# 1__schdoc.net
KiCad netlist of a schematic drawn in Altium Designer
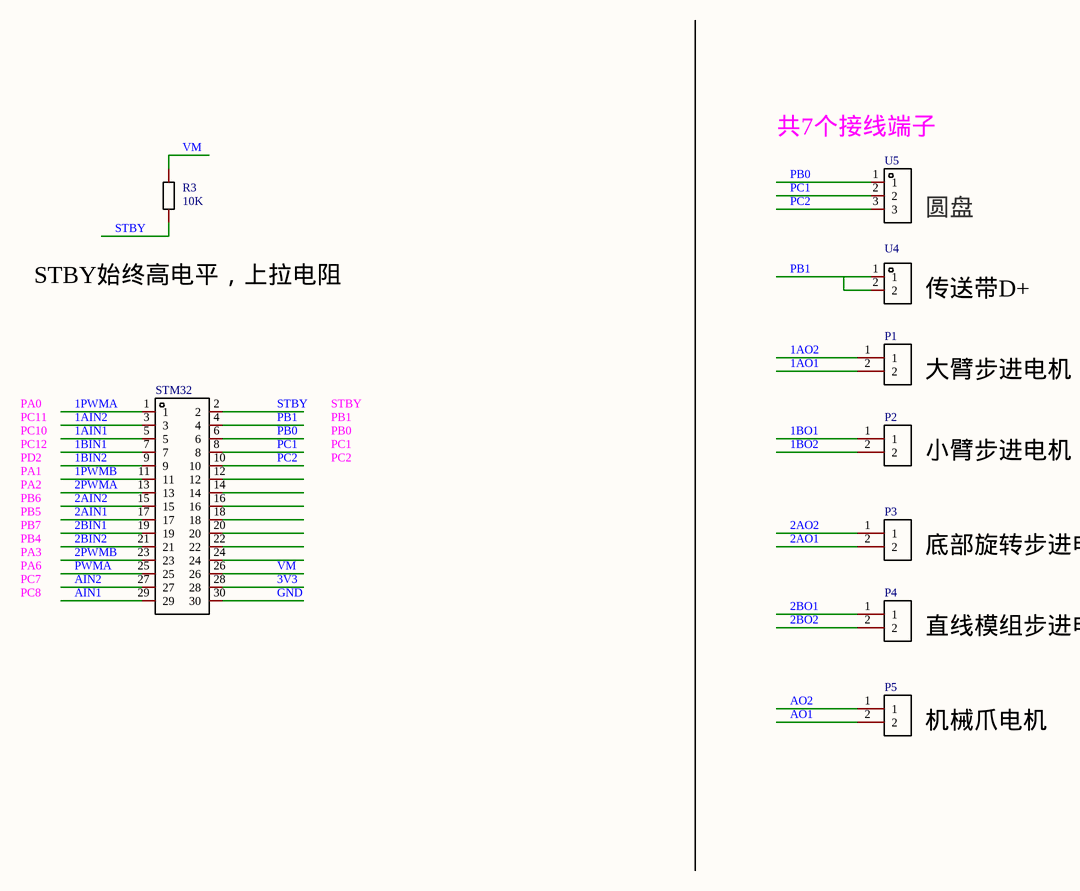
[diagram p0: 1_接口.schdoc.schdoc]

(export (version "E")
  (design (tool "Eeschema 10.0.6"))
  (components
    (comp (ref "P1")
      (value "WJ500V-5.08-2P")
      (fields (field (name "MANUFACTURER") "KANGNEX(康奈克斯电气)"))
      (libsource (lib "altium-import") (part "root_3_WJ500V-5.08-2P_"))
    )
    (comp (ref "P2")
      (value "WJ500V-5.08-2P")
      (fields (field (name "MANUFACTURER") "KANGNEX(康奈克斯电气)"))
      (libsource (lib "altium-import") (part "root_3_WJ500V-5.08-2P_"))
    )
    (comp (ref "P3")
      (value "WJ500V-5.08-2P")
      (fields (field (name "MANUFACTURER") "KANGNEX(康奈克斯电气)"))
      (libsource (lib "altium-import") (part "root_3_WJ500V-5.08-2P_"))
    )
    (comp (ref "P4")
      (value "WJ500V-5.08-2P")
      (fields (field (name "MANUFACTURER") "KANGNEX(康奈克斯电气)"))
      (libsource (lib "altium-import") (part "root_3_WJ500V-5.08-2P_"))
    )
    (comp (ref "P5")
      (value "WJ500V-5.08-2P")
      (fields (field (name "MANUFACTURER") "KANGNEX(康奈克斯电气)"))
      (libsource (lib "altium-import") (part "root_3_WJ500V-5.08-2P_"))
    )
    (comp (ref "R3")
      (value "10K")
      (fields (field (name "NAME") "10K"))
      (libsource (lib "altium-import") (part "root_1_Res_0603_"))
    )
    (comp (ref "STM32")
      (value "PM254-2-15-Z-8.5")
      (fields (field (name "MANUFACTURER") "HCTL(华灿天禄)"))
      (libsource (lib "altium-import") (part "root_0_PM254-2-15-Z-8.5_"))
    )
    (comp (ref "U4")
      (value "DB136HA-10.16-1P-S")
      (description "结构:1x1P;间距:10.16mm;颜色:绿色;安装方式:直插;额定电流:65A;额定电压:600V;排数:1;线规 - AWG:6~20;每排PIN数:1;工作温度范围:-40℃~+105℃;")
      (fields (field (name "MANUFACTURER") "DORABO(地博电气)"))
      (libsource (lib "altium-import") (part "root_0_DB136HA-10.16-1P-S_"))
    )
    (comp (ref "U5")
      (value "XY128V-A-5.08-3P")
      (fields (field (name "MANUFACTURER") "XINLAIYA(新莱亚)"))
      (libsource (lib "altium-import") (part "root_0_XY128V-A-5.08-3P_"))
    )
  )
  (nets
    (net (code "1") (name "/1AIN1") (class "Default")
      (node (ref "STM32") (pin "5") (pinfunction "5_5") (pintype "passive"))
    )
    (net (code "2") (name "/1AIN2") (class "Default")
      (node (ref "STM32") (pin "3") (pinfunction "3_3") (pintype "passive"))
    )
    (net (code "3") (name "/1AO1") (class "Default")
      (node (ref "P1") (pin "2") (pinfunction "2_2") (pintype "passive"))
    )
    (net (code "4") (name "/1AO2") (class "Default")
      (node (ref "P1") (pin "1") (pinfunction "1_1") (pintype "passive"))
    )
    (net (code "5") (name "/1BIN1") (class "Default")
      (node (ref "STM32") (pin "7") (pinfunction "7_7") (pintype "passive"))
    )
    (net (code "6") (name "/1BIN2") (class "Default")
      (node (ref "STM32") (pin "9") (pinfunction "9_9") (pintype "passive"))
    )
    (net (code "7") (name "/1BO1") (class "Default")
      (node (ref "P2") (pin "1") (pinfunction "1_1") (pintype "passive"))
    )
    (net (code "8") (name "/1BO2") (class "Default")
      (node (ref "P2") (pin "2") (pinfunction "2_2") (pintype "passive"))
    )
    (net (code "9") (name "/1PWMA") (class "Default")
      (node (ref "STM32") (pin "1") (pinfunction "1_1") (pintype "passive"))
    )
    (net (code "10") (name "/1PWMB") (class "Default")
      (node (ref "STM32") (pin "11") (pinfunction "11_11") (pintype "passive"))
    )
    (net (code "11") (name "/2AIN1") (class "Default")
      (node (ref "STM32") (pin "17") (pinfunction "17_17") (pintype "passive"))
    )
    (net (code "12") (name "/2AIN2") (class "Default")
      (node (ref "STM32") (pin "15") (pinfunction "15_15") (pintype "passive"))
    )
    (net (code "13") (name "/2AO1") (class "Default")
      (node (ref "P3") (pin "2") (pinfunction "2_2") (pintype "passive"))
    )
    (net (code "14") (name "/2AO2") (class "Default")
      (node (ref "P3") (pin "1") (pinfunction "1_1") (pintype "passive"))
    )
    (net (code "15") (name "/2BIN1") (class "Default")
      (node (ref "STM32") (pin "19") (pinfunction "19_19") (pintype "passive"))
    )
    (net (code "16") (name "/2BIN2") (class "Default")
      (node (ref "STM32") (pin "21") (pinfunction "21_21") (pintype "passive"))
    )
    (net (code "17") (name "/2BO1") (class "Default")
      (node (ref "P4") (pin "1") (pinfunction "1_1") (pintype "passive"))
    )
    (net (code "18") (name "/2BO2") (class "Default")
      (node (ref "P4") (pin "2") (pinfunction "2_2") (pintype "passive"))
    )
    (net (code "19") (name "/2PWMA") (class "Default")
      (node (ref "STM32") (pin "13") (pinfunction "13_13") (pintype "passive"))
    )
    (net (code "20") (name "/2PWMB") (class "Default")
      (node (ref "STM32") (pin "23") (pinfunction "23_23") (pintype "passive"))
    )
    (net (code "21") (name "/3V3") (class "Default")
      (node (ref "STM32") (pin "28") (pinfunction "28_28") (pintype "passive"))
    )
    (net (code "22") (name "/AIN1") (class "Default")
      (node (ref "STM32") (pin "29") (pinfunction "29_29") (pintype "passive"))
    )
    (net (code "23") (name "/AIN2") (class "Default")
      (node (ref "STM32") (pin "27") (pinfunction "27_27") (pintype "passive"))
    )
    (net (code "24") (name "/AO1") (class "Default")
      (node (ref "P5") (pin "2") (pinfunction "2_2") (pintype "passive"))
    )
    (net (code "25") (name "/AO2") (class "Default")
      (node (ref "P5") (pin "1") (pinfunction "1_1") (pintype "passive"))
    )
    (net (code "26") (name "/GND") (class "Default")
      (node (ref "STM32") (pin "30") (pinfunction "30_30") (pintype "passive"))
    )
    (net (code "27") (name "/PB0") (class "Default")
      (node (ref "STM32") (pin "6") (pinfunction "6_6") (pintype "passive"))
      (node (ref "U5") (pin "1") (pinfunction "1_1") (pintype "passive"))
    )
    (net (code "28") (name "/PB1") (class "Default")
      (node (ref "STM32") (pin "4") (pinfunction "4_4") (pintype "passive"))
      (node (ref "U4") (pin "1") (pinfunction "1_1") (pintype "passive"))
      (node (ref "U4") (pin "2") (pinfunction "2_2") (pintype "passive"))
    )
    (net (code "29") (name "/PC1") (class "Default")
      (node (ref "STM32") (pin "8") (pinfunction "8_8") (pintype "passive"))
      (node (ref "U5") (pin "2") (pinfunction "2_2") (pintype "passive"))
    )
    (net (code "30") (name "/PC2") (class "Default")
      (node (ref "STM32") (pin "10") (pinfunction "10_10") (pintype "passive"))
      (node (ref "U5") (pin "3") (pinfunction "3_3") (pintype "passive"))
    )
    (net (code "31") (name "/PWMA") (class "Default")
      (node (ref "STM32") (pin "25") (pinfunction "25_25") (pintype "passive"))
    )
    (net (code "32") (name "/STBY") (class "Default")
      (node (ref "R3") (pin "1") (pinfunction "1_1") (pintype "passive"))
      (node (ref "STM32") (pin "2") (pinfunction "2_2") (pintype "passive"))
    )
    (net (code "33") (name "/VM") (class "Default")
      (node (ref "R3") (pin "2") (pinfunction "2_2") (pintype "passive"))
      (node (ref "STM32") (pin "26") (pinfunction "26_26") (pintype "passive"))
    )
    (net (code "34") (name "unconnected-(STM32-Pad12)") (class "Default")
      (node (ref "STM32") (pin "12") (pinfunction "12_12") (pintype "passive"))
    )
    (net (code "35") (name "unconnected-(STM32-Pad14)") (class "Default")
      (node (ref "STM32") (pin "14") (pinfunction "14_14") (pintype "passive"))
    )
    (net (code "36") (name "unconnected-(STM32-Pad16)") (class "Default")
      (node (ref "STM32") (pin "16") (pinfunction "16_16") (pintype "passive"))
    )
    (net (code "37") (name "unconnected-(STM32-Pad18)") (class "Default")
      (node (ref "STM32") (pin "18") (pinfunction "18_18") (pintype "passive"))
    )
    (net (code "38") (name "unconnected-(STM32-Pad20)") (class "Default")
      (node (ref "STM32") (pin "20") (pinfunction "20_20") (pintype "passive"))
    )
    (net (code "39") (name "unconnected-(STM32-Pad22)") (class "Default")
      (node (ref "STM32") (pin "22") (pinfunction "22_22") (pintype "passive"))
    )
    (net (code "40") (name "unconnected-(STM32-Pad24)") (class "Default")
      (node (ref "STM32") (pin "24") (pinfunction "24_24") (pintype "passive"))
    )
  )
)
